# Control_Board.net
KiCad netlist of a schematic drawn in Altium Designer
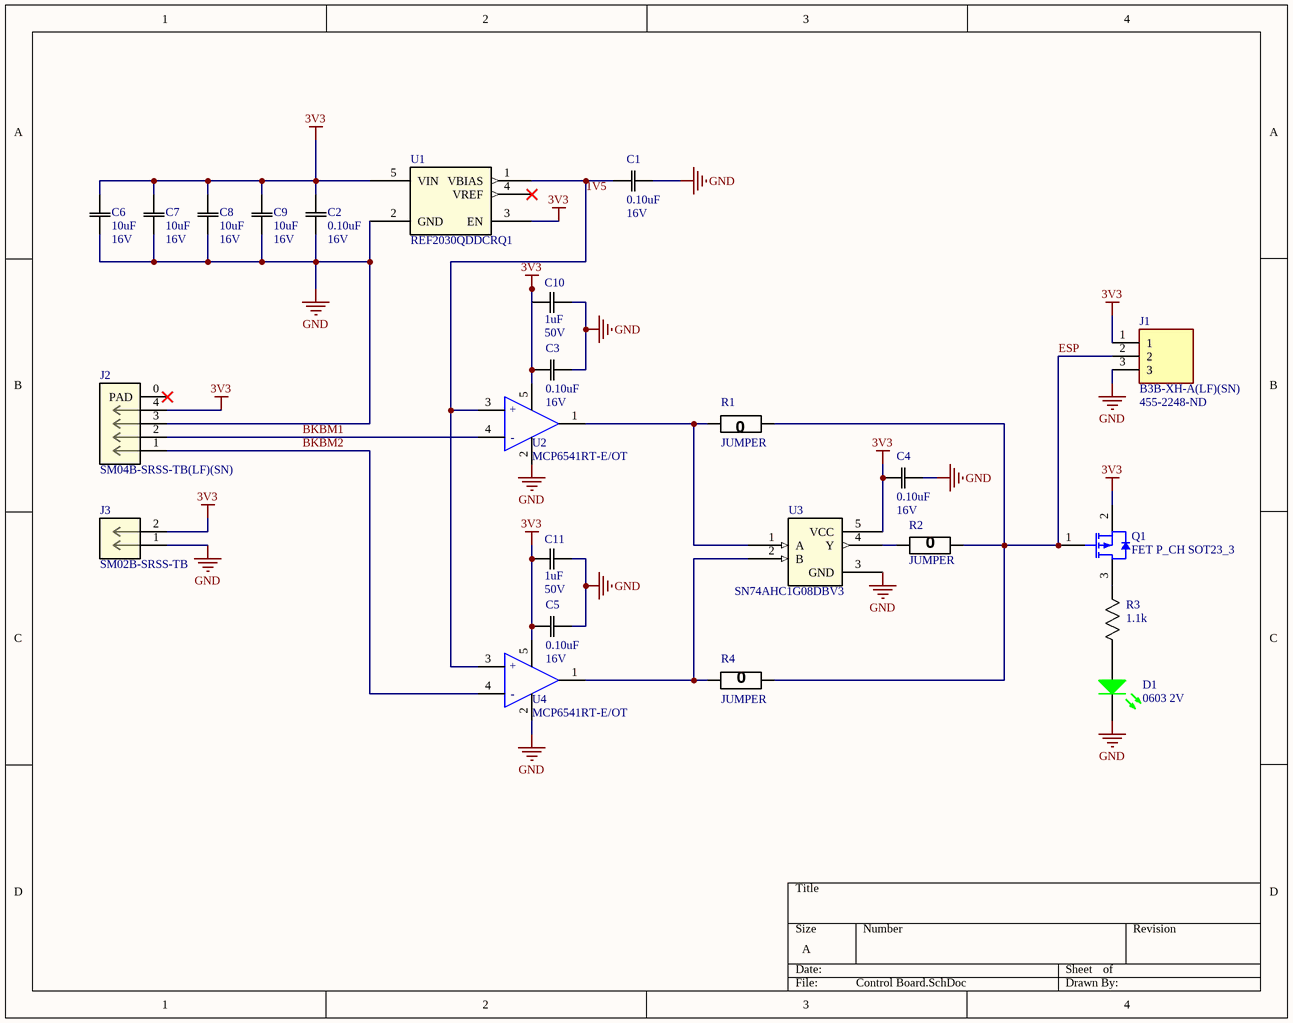
[diagram p0: Control Board.SchDoc]

(export (version "E")
  (design (tool "Eeschema 10.0.6"))
  (components
    (comp (ref "C1")
      (value "0.10uF")
      (footprint "0603")
      (description "CAP CER 0.10UF 16V X5R 0603")
      (fields
        (field (name "TOLERANCE") "10%")
        (field (name "RATING") "16V")
        (field (name "PART NUMBER") "CAP 0.10uF 16V")
      )
      (libsource (lib "capacitor_library") (part "CAP 0.10uF 16V"))
    )
    (comp (ref "C2")
      (value "0.10uF")
      (footprint "0603")
      (description "CAP CER 0.10UF 16V X5R 0603")
      (fields
        (field (name "TOLERANCE") "10%")
        (field (name "RATING") "16V")
        (field (name "PART NUMBER") "CAP 0.10uF 16V")
      )
      (libsource (lib "capacitor_library") (part "CAP 0.10uF 16V"))
    )
    (comp (ref "C3")
      (value "0.10uF")
      (footprint "0603")
      (description "CAP CER 0.10UF 16V X5R 0603")
      (fields
        (field (name "TOLERANCE") "10%")
        (field (name "RATING") "16V")
        (field (name "PART NUMBER") "CAP 0.10uF 16V")
      )
      (libsource (lib "capacitor_library") (part "CAP 0.10uF 16V"))
    )
    (comp (ref "C4")
      (value "0.10uF")
      (footprint "0603")
      (description "CAP CER 0.10UF 16V X5R 0603")
      (fields
        (field (name "TOLERANCE") "10%")
        (field (name "RATING") "16V")
        (field (name "PART NUMBER") "CAP 0.10uF 16V")
      )
      (libsource (lib "capacitor_library") (part "CAP 0.10uF 16V"))
    )
    (comp (ref "C5")
      (value "0.10uF")
      (footprint "0603")
      (description "CAP CER 0.10UF 16V X5R 0603")
      (fields
        (field (name "TOLERANCE") "10%")
        (field (name "RATING") "16V")
        (field (name "PART NUMBER") "CAP 0.10uF 16V")
      )
      (libsource (lib "capacitor_library") (part "CAP 0.10uF 16V"))
    )
    (comp (ref "C6")
      (value "10uF")
      (footprint "0603")
      (description "CAP CER 10UF 16V X5R 0603/0805")
      (fields
        (field (name "TOLERANCE") "10%")
        (field (name "RATING") "16V")
        (field (name "PART NUMBER") "CAP 10uF 16V")
      )
      (libsource (lib "capacitor_library") (part "CAP 10uF 16V"))
    )
    (comp (ref "C7")
      (value "10uF")
      (footprint "0603")
      (description "CAP CER 10UF 16V X5R 0603/0805")
      (fields
        (field (name "TOLERANCE") "10%")
        (field (name "RATING") "16V")
        (field (name "PART NUMBER") "CAP 10uF 16V")
      )
      (libsource (lib "capacitor_library") (part "CAP 10uF 16V"))
    )
    (comp (ref "C8")
      (value "10uF")
      (footprint "0603")
      (description "CAP CER 10UF 16V X5R 0603/0805")
      (fields
        (field (name "TOLERANCE") "10%")
        (field (name "RATING") "16V")
        (field (name "PART NUMBER") "CAP 10uF 16V")
      )
      (libsource (lib "capacitor_library") (part "CAP 10uF 16V"))
    )
    (comp (ref "C9")
      (value "10uF")
      (footprint "0603")
      (description "CAP CER 10UF 16V X5R 0603/0805")
      (fields
        (field (name "TOLERANCE") "10%")
        (field (name "RATING") "16V")
        (field (name "PART NUMBER") "CAP 10uF 16V")
      )
      (libsource (lib "capacitor_library") (part "CAP 10uF 16V"))
    )
    (comp (ref "C10")
      (value "1uF")
      (footprint "0603")
      (description "Default Symbol for Capacitors")
      (fields
        (field (name "RATING") "50V")
        (field (name "PART NUMBER") "CAP 1uF 50V")
        (field (name "TOLERANCE") "10%")
      )
      (libsource (lib "capacitor_library") (part "CAP_Default"))
    )
    (comp (ref "C11")
      (value "1uF")
      (footprint "0603")
      (description "Default Symbol for Capacitors")
      (fields
        (field (name "RATING") "50V")
        (field (name "PART NUMBER") "CAP 1uF 50V")
        (field (name "TOLERANCE") "10%")
      )
      (libsource (lib "capacitor_library") (part "CAP_Default"))
    )
    (comp (ref "D1")
      (value "0603 2V")
      (footprint "0603 - LED")
      (description "LED Uni-Color Green 574nm 2-Pin Chip LED T/R")
      (fields (field (name "PART NUMBER") "LED GREEN SMD 0603"))
      (libsource (lib "Diode_Library") (part "LED GREEN SMD 0603"))
    )
    (comp (ref "J1")
      (value "B3B-XH-A(LF)(SN)")
      (footprint "JST_B3B-XH-A(LF)(SN)")
      (description "Connector Header Through Hole 3 position 0.098 (2.50mm)")
      (fields
        (field (name "MF") "JST Sales")
        (field (name "SUPPLIER PART NUMBER 1") "455-2248-ND")
        (field (name "PART NUMBER") "CN HDR 3POS JST XH")
      )
      (libsource (lib "Connector_Library") (part "CN HDR 3POS JST XH"))
    )
    (comp (ref "J2")
      (value "SM04B-SRSS-TB(LF)(SN)")
      (footprint "CONN_SM04B_JST")
      (description "CONN HEADER SMD R/A 4POS 1MM")
      (fields
        (field (name "PART NUMBER") "CN HDR 4POS JST SH_SR")
        (field (name "COPYRIGHT") "Copyright (C) 2023 Ultra Librarian. All rights reserved.")
      )
      (libsource (lib "Connector_Library") (part "CN HDR 4POS JST SH_SR"))
    )
    (comp (ref "J3")
      (value "SM02B-SRSS-TB")
      (footprint "SM02B-SRSS-TB(LF)(SN)")
      (description "No Description Available")
      (fields
        (field (name "PART NUMBER") "CN HDR 2POS 90 JST SH")
        (field (name "COPYRIGHT") "Copyright (C) 2023 Ultra Librarian. All rights reserved.")
      )
      (libsource (lib "Connector_Library") (part "CN HDR 2POS 90 JST SH"))
    )
    (comp (ref "Q1")
      (value "FET P_CH SOT23_3")
      (footprint "SOT-23A-3")
      (description "P-Channel MOSFET General Purpose P-CH SOT23-3")
      (fields (field (name "PART NUMBER") "MOSFET P-CH CJ2305"))
      (libsource (lib "Transistor_Library") (part "FET P_CH SOT23_3"))
    )
    (comp (ref "R1")
      (value "JUMPER")
      (footprint "0603")
      (description "RES SMD 0 OHM JUMPER GENERIC 0603")
      (fields (field (name "PART NUMBER") "RES 0 JUMPER"))
      (libsource (lib "Resistor_Library") (part "RES 0 JUMPER"))
    )
    (comp (ref "R2")
      (value "JUMPER")
      (footprint "0603")
      (description "RES SMD 0 OHM JUMPER GENERIC 0603")
      (fields (field (name "PART NUMBER") "RES 0 JUMPER"))
      (libsource (lib "Resistor_Library") (part "RES 0 JUMPER"))
    )
    (comp (ref "R3")
      (value "1.1k")
      (footprint "0603")
      (description "Default Resistor Symbol")
      (fields (field (name "TOLERANCE") "5%") (field (name "PART NUMBER") "RES 1.1k 1/8W"))
      (libsource (lib "Resistor_Library") (part "RES_DEFAULT"))
    )
    (comp (ref "R4")
      (value "JUMPER")
      (footprint "0603")
      (description "RES SMD 0 OHM JUMPER GENERIC 0603")
      (fields (field (name "PART NUMBER") "RES 0 JUMPER"))
      (libsource (lib "Resistor_Library") (part "RES 0 JUMPER"))
    )
    (comp (ref "U1")
      (value "REF2030QDDCRQ1")
      (footprint "SOT-23-5_MC_MCH-L")
      (description "Series Voltage Reference IC Fixed 1.5V, 3V V ±0.05% 20 mA SOT-23-THIN")
      (fields
        (field (name "MANUFACTURER_PART_NUMBER") "SN74AHC1G08DBV3")
        (field (name "COPYRIGHT") "Copyright (C) 2023 Ultra Librarian. All rights reserved.")
      )
      (libsource (lib "IC_Library") (part "REF2030QDDCRQ1"))
    )
    (comp (ref "U2")
      (value "MCP6541RT-E/OT")
      (footprint "SOT-23-5_MC_MCH-L")
      (description "IC COMP 1.6V SNGL P-P SOT23-5")
      (fields (field (name "PART NUMBER") "COMPARATOR MCP6541RT-EOT"))
      (libsource (lib "IC_Library") (part "COMPARATOR MCP6541RT-EOT"))
    )
    (comp (ref "U3")
      (value "SN74AHC1G08DBV3")
      (footprint "SOT-23-5_MC_MCH-L")
      (description "IC GATE AND 1CH 2-INP SOT23-5")
      (fields (field (name "COPYRIGHT") "Copyright (C) 2023 Ultra Librarian. All rights reserved."))
      (libsource (lib "IC_Library") (part "SN74AHC1G08DBV3"))
    )
    (comp (ref "U4")
      (value "MCP6541RT-E/OT")
      (footprint "SOT-23-5_MC_MCH-L")
      (description "IC COMP 1.6V SNGL P-P SOT23-5")
      (fields (field (name "PART NUMBER") "COMPARATOR MCP6541RT-EOT"))
      (libsource (lib "IC_Library") (part "COMPARATOR MCP6541RT-EOT"))
    )
  )
  (nets
    (net (code "1") (name "/1V5") (class "Default")
      (node (ref "C1") (pin "2") (pinfunction "C2_2") (pintype "passive"))
      (node (ref "U1") (pin "1") (pinfunction "VBIAS_1") (pintype "output"))
      (node (ref "U2") (pin "3") (pinfunction "IN+_3") (pintype "tri_state"))
      (node (ref "U4") (pin "3") (pinfunction "IN+_3") (pintype "tri_state"))
    )
    (net (code "2") (name "/BKBM1") (class "Default")
      (node (ref "J2") (pin "2") (pinfunction "2_2") (pintype "passive"))
      (node (ref "U2") (pin "4") (pinfunction "IN-_4") (pintype "tri_state"))
    )
    (net (code "3") (name "/BKBM2") (class "Default")
      (node (ref "J2") (pin "1") (pinfunction "1_1") (pintype "passive"))
      (node (ref "U4") (pin "4") (pinfunction "IN-_4") (pintype "tri_state"))
    )
    (net (code "4") (name "/ESP") (class "Default")
      (node (ref "J1") (pin "2") (pinfunction "2_2") (pintype "passive"))
      (node (ref "Q1") (pin "1") (pinfunction "GATE_1") (pintype "passive"))
      (node (ref "R1") (pin "1") (pinfunction "R1_1") (pintype "passive"))
      (node (ref "R2") (pin "2") (pinfunction "R2_2") (pintype "passive"))
      (node (ref "R4") (pin "2") (pinfunction "R2_2") (pintype "passive"))
    )
    (net (code "5") (name "3V3") (class "Default")
      (node (ref "C10") (pin "1") (pinfunction "C1_1") (pintype "passive"))
      (node (ref "C11") (pin "1") (pinfunction "C1_1") (pintype "passive"))
      (node (ref "C2") (pin "1") (pinfunction "C1_1") (pintype "passive"))
      (node (ref "C3") (pin "2") (pinfunction "C2_2") (pintype "passive"))
      (node (ref "C4") (pin "2") (pinfunction "C2_2") (pintype "passive"))
      (node (ref "C5") (pin "2") (pinfunction "C2_2") (pintype "passive"))
      (node (ref "C6") (pin "2") (pinfunction "C2_2") (pintype "passive"))
      (node (ref "C7") (pin "2") (pinfunction "C2_2") (pintype "passive"))
      (node (ref "C8") (pin "2") (pinfunction "C2_2") (pintype "passive"))
      (node (ref "C9") (pin "2") (pinfunction "C2_2") (pintype "passive"))
      (node (ref "J1") (pin "1") (pinfunction "1_1") (pintype "passive"))
      (node (ref "J2") (pin "4") (pinfunction "4_4") (pintype "passive"))
      (node (ref "J3") (pin "2") (pinfunction "2_2") (pintype "passive"))
      (node (ref "Q1") (pin "2") (pinfunction "SOURCE_2") (pintype "passive"))
      (node (ref "U1") (pin "3") (pinfunction "EN_3") (pintype "power_in"))
      (node (ref "U1") (pin "5") (pinfunction "VIN_5") (pintype "power_in"))
      (node (ref "U2") (pin "5") (pinfunction "V+_5") (pintype "power_in"))
      (node (ref "U3") (pin "5") (pinfunction "VCC_5") (pintype "power_in"))
      (node (ref "U4") (pin "5") (pinfunction "V+_5") (pintype "power_in"))
    )
    (net (code "6") (name "GND") (class "Default")
      (node (ref "C1") (pin "1") (pinfunction "C1_1") (pintype "passive"))
      (node (ref "C10") (pin "2") (pinfunction "C2_2") (pintype "passive"))
      (node (ref "C11") (pin "2") (pinfunction "C2_2") (pintype "passive"))
      (node (ref "C2") (pin "2") (pinfunction "C2_2") (pintype "passive"))
      (node (ref "C3") (pin "1") (pinfunction "C1_1") (pintype "passive"))
      (node (ref "C4") (pin "1") (pinfunction "C1_1") (pintype "passive"))
      (node (ref "C5") (pin "1") (pinfunction "C1_1") (pintype "passive"))
      (node (ref "C6") (pin "1") (pinfunction "C1_1") (pintype "passive"))
      (node (ref "C7") (pin "1") (pinfunction "C1_1") (pintype "passive"))
      (node (ref "C8") (pin "1") (pinfunction "C1_1") (pintype "passive"))
      (node (ref "C9") (pin "1") (pinfunction "C1_1") (pintype "passive"))
      (node (ref "D1") (pin "2") (pinfunction "K_2") (pintype "passive"))
      (node (ref "J1") (pin "3") (pinfunction "3_3") (pintype "passive"))
      (node (ref "J2") (pin "3") (pinfunction "3_3") (pintype "passive"))
      (node (ref "J3") (pin "1") (pinfunction "1_1") (pintype "passive"))
      (node (ref "U1") (pin "2") (pinfunction "GND_2") (pintype "power_in"))
      (node (ref "U2") (pin "2") (pinfunction "V-_2") (pintype "power_in"))
      (node (ref "U3") (pin "3") (pinfunction "GND_3") (pintype "power_in"))
      (node (ref "U4") (pin "2") (pinfunction "V-_2") (pintype "power_in"))
    )
    (net (code "7") (name "Net-(D1-A)") (class "Default")
      (node (ref "D1") (pin "1") (pinfunction "A_1") (pintype "passive"))
      (node (ref "R3") (pin "2") (pinfunction "R2_2") (pintype "passive"))
    )
    (net (code "8") (name "Net-(Q1-DRAIN)") (class "Default")
      (node (ref "Q1") (pin "3") (pinfunction "DRAIN_3") (pintype "passive"))
      (node (ref "R3") (pin "1") (pinfunction "R1_1") (pintype "passive"))
    )
    (net (code "9") (name "Net-(R1-R2)") (class "Default")
      (node (ref "R1") (pin "2") (pinfunction "R2_2") (pintype "passive"))
      (node (ref "U2") (pin "1") (pinfunction "OUT_1") (pintype "passive"))
      (node (ref "U3") (pin "1") (pinfunction "A_1") (pintype "input"))
    )
    (net (code "10") (name "Net-(R2-R1)") (class "Default")
      (node (ref "R2") (pin "1") (pinfunction "R1_1") (pintype "passive"))
      (node (ref "U3") (pin "4") (pinfunction "Y_4") (pintype "output"))
    )
    (net (code "11") (name "Net-(R4-R1)") (class "Default")
      (node (ref "R4") (pin "1") (pinfunction "R1_1") (pintype "passive"))
      (node (ref "U3") (pin "2") (pinfunction "B_2") (pintype "input"))
      (node (ref "U4") (pin "1") (pinfunction "OUT_1") (pintype "passive"))
    )
    (net (code "12") (name "unconnected-(J2-PAD-Pad0)") (class "Default")
      (node (ref "J2") (pin "0") (pinfunction "PAD_0") (pintype "passive+no_connect"))
    )
    (net (code "13") (name "unconnected-(U1-VREF-Pad4)") (class "Default")
      (node (ref "U1") (pin "4") (pinfunction "VREF_4") (pintype "output+no_connect"))
    )
  )
)
